# CONNECTOR.net
KiCad netlist of a schematic drawn in Altium Designer
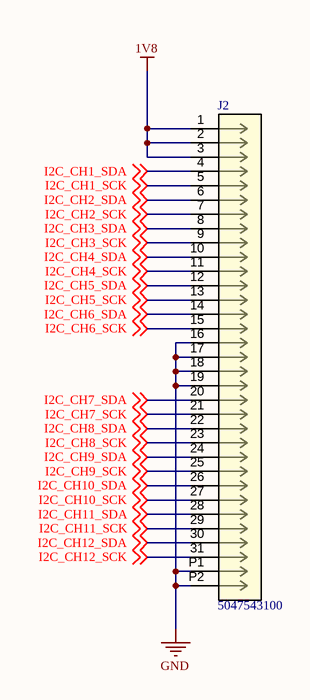
[diagram p0: CONNECTOR.SchDoc]

(export (version "E")
  (design (tool "Eeschema 10.0.6"))
  (components
    (comp (ref "J2")
      (value "5047543100")
      (footprint "CON_5047543100_MOL")
      (description "No Description Available")
      (libsource (lib "5047543100") (part "5047543100"))
    )
  )
  (nets
    (net (code "1") (name "1V8") (class "Default")
      (node (ref "J2") (pin "1") (pinfunction "1_1") (pintype "passive"))
      (node (ref "J2") (pin "2") (pinfunction "2_2") (pintype "passive"))
      (node (ref "J2") (pin "3") (pinfunction "3_3") (pintype "passive"))
    )
    (net (code "2") (name "GND") (class "Default")
      (node (ref "J2") (pin "16") (pinfunction "16_16") (pintype "passive"))
      (node (ref "J2") (pin "17") (pinfunction "17_17") (pintype "passive"))
      (node (ref "J2") (pin "18") (pinfunction "18_18") (pintype "passive"))
      (node (ref "J2") (pin "19") (pinfunction "19_19") (pintype "passive"))
      (node (ref "J2") (pin "P1") (pinfunction "P1_P1") (pintype "passive"))
      (node (ref "J2") (pin "P2") (pinfunction "P2_P2") (pintype "passive"))
    )
    (net (code "3") (name "I2C_CH1_SCK") (class "Default")
      (node (ref "J2") (pin "5") (pinfunction "5_5") (pintype "passive"))
    )
    (net (code "4") (name "I2C_CH1_SDA") (class "Default")
      (node (ref "J2") (pin "4") (pinfunction "4_4") (pintype "passive"))
    )
    (net (code "5") (name "I2C_CH2_SCK") (class "Default")
      (node (ref "J2") (pin "7") (pinfunction "7_7") (pintype "passive"))
    )
    (net (code "6") (name "I2C_CH2_SDA") (class "Default")
      (node (ref "J2") (pin "6") (pinfunction "6_6") (pintype "passive"))
    )
    (net (code "7") (name "I2C_CH3_SCK") (class "Default")
      (node (ref "J2") (pin "9") (pinfunction "9_9") (pintype "passive"))
    )
    (net (code "8") (name "I2C_CH3_SDA") (class "Default")
      (node (ref "J2") (pin "8") (pinfunction "8_8") (pintype "passive"))
    )
    (net (code "9") (name "I2C_CH4_SCK") (class "Default")
      (node (ref "J2") (pin "11") (pinfunction "11_11") (pintype "passive"))
    )
    (net (code "10") (name "I2C_CH4_SDA") (class "Default")
      (node (ref "J2") (pin "10") (pinfunction "10_10") (pintype "passive"))
    )
    (net (code "11") (name "I2C_CH5_SCK") (class "Default")
      (node (ref "J2") (pin "13") (pinfunction "13_13") (pintype "passive"))
    )
    (net (code "12") (name "I2C_CH5_SDA") (class "Default")
      (node (ref "J2") (pin "12") (pinfunction "12_12") (pintype "passive"))
    )
    (net (code "13") (name "I2C_CH6_SCK") (class "Default")
      (node (ref "J2") (pin "15") (pinfunction "15_15") (pintype "passive"))
    )
    (net (code "14") (name "I2C_CH6_SDA") (class "Default")
      (node (ref "J2") (pin "14") (pinfunction "14_14") (pintype "passive"))
    )
    (net (code "15") (name "I2C_CH7_SCK") (class "Default")
      (node (ref "J2") (pin "21") (pinfunction "21_21") (pintype "passive"))
    )
    (net (code "16") (name "I2C_CH7_SDA") (class "Default")
      (node (ref "J2") (pin "20") (pinfunction "20_20") (pintype "passive"))
    )
    (net (code "17") (name "I2C_CH8_SCK") (class "Default")
      (node (ref "J2") (pin "23") (pinfunction "23_23") (pintype "passive"))
    )
    (net (code "18") (name "I2C_CH8_SDA") (class "Default")
      (node (ref "J2") (pin "22") (pinfunction "22_22") (pintype "passive"))
    )
    (net (code "19") (name "I2C_CH9_SCK") (class "Default")
      (node (ref "J2") (pin "25") (pinfunction "25_25") (pintype "passive"))
    )
    (net (code "20") (name "I2C_CH9_SDA") (class "Default")
      (node (ref "J2") (pin "24") (pinfunction "24_24") (pintype "passive"))
    )
    (net (code "21") (name "I2C_CH10_SCK") (class "Default")
      (node (ref "J2") (pin "27") (pinfunction "27_27") (pintype "passive"))
    )
    (net (code "22") (name "I2C_CH10_SDA") (class "Default")
      (node (ref "J2") (pin "26") (pinfunction "26_26") (pintype "passive"))
    )
    (net (code "23") (name "I2C_CH11_SCK") (class "Default")
      (node (ref "J2") (pin "29") (pinfunction "29_29") (pintype "passive"))
    )
    (net (code "24") (name "I2C_CH11_SDA") (class "Default")
      (node (ref "J2") (pin "28") (pinfunction "28_28") (pintype "passive"))
    )
    (net (code "25") (name "I2C_CH12_SCK") (class "Default")
      (node (ref "J2") (pin "31") (pinfunction "31_31") (pintype "passive"))
    )
    (net (code "26") (name "I2C_CH12_SDA") (class "Default")
      (node (ref "J2") (pin "30") (pinfunction "30_30") (pintype "passive"))
    )
  )
)
